# OPENMV4_BASE_ascii.net
KiCad netlist of a schematic drawn in Altium Designer
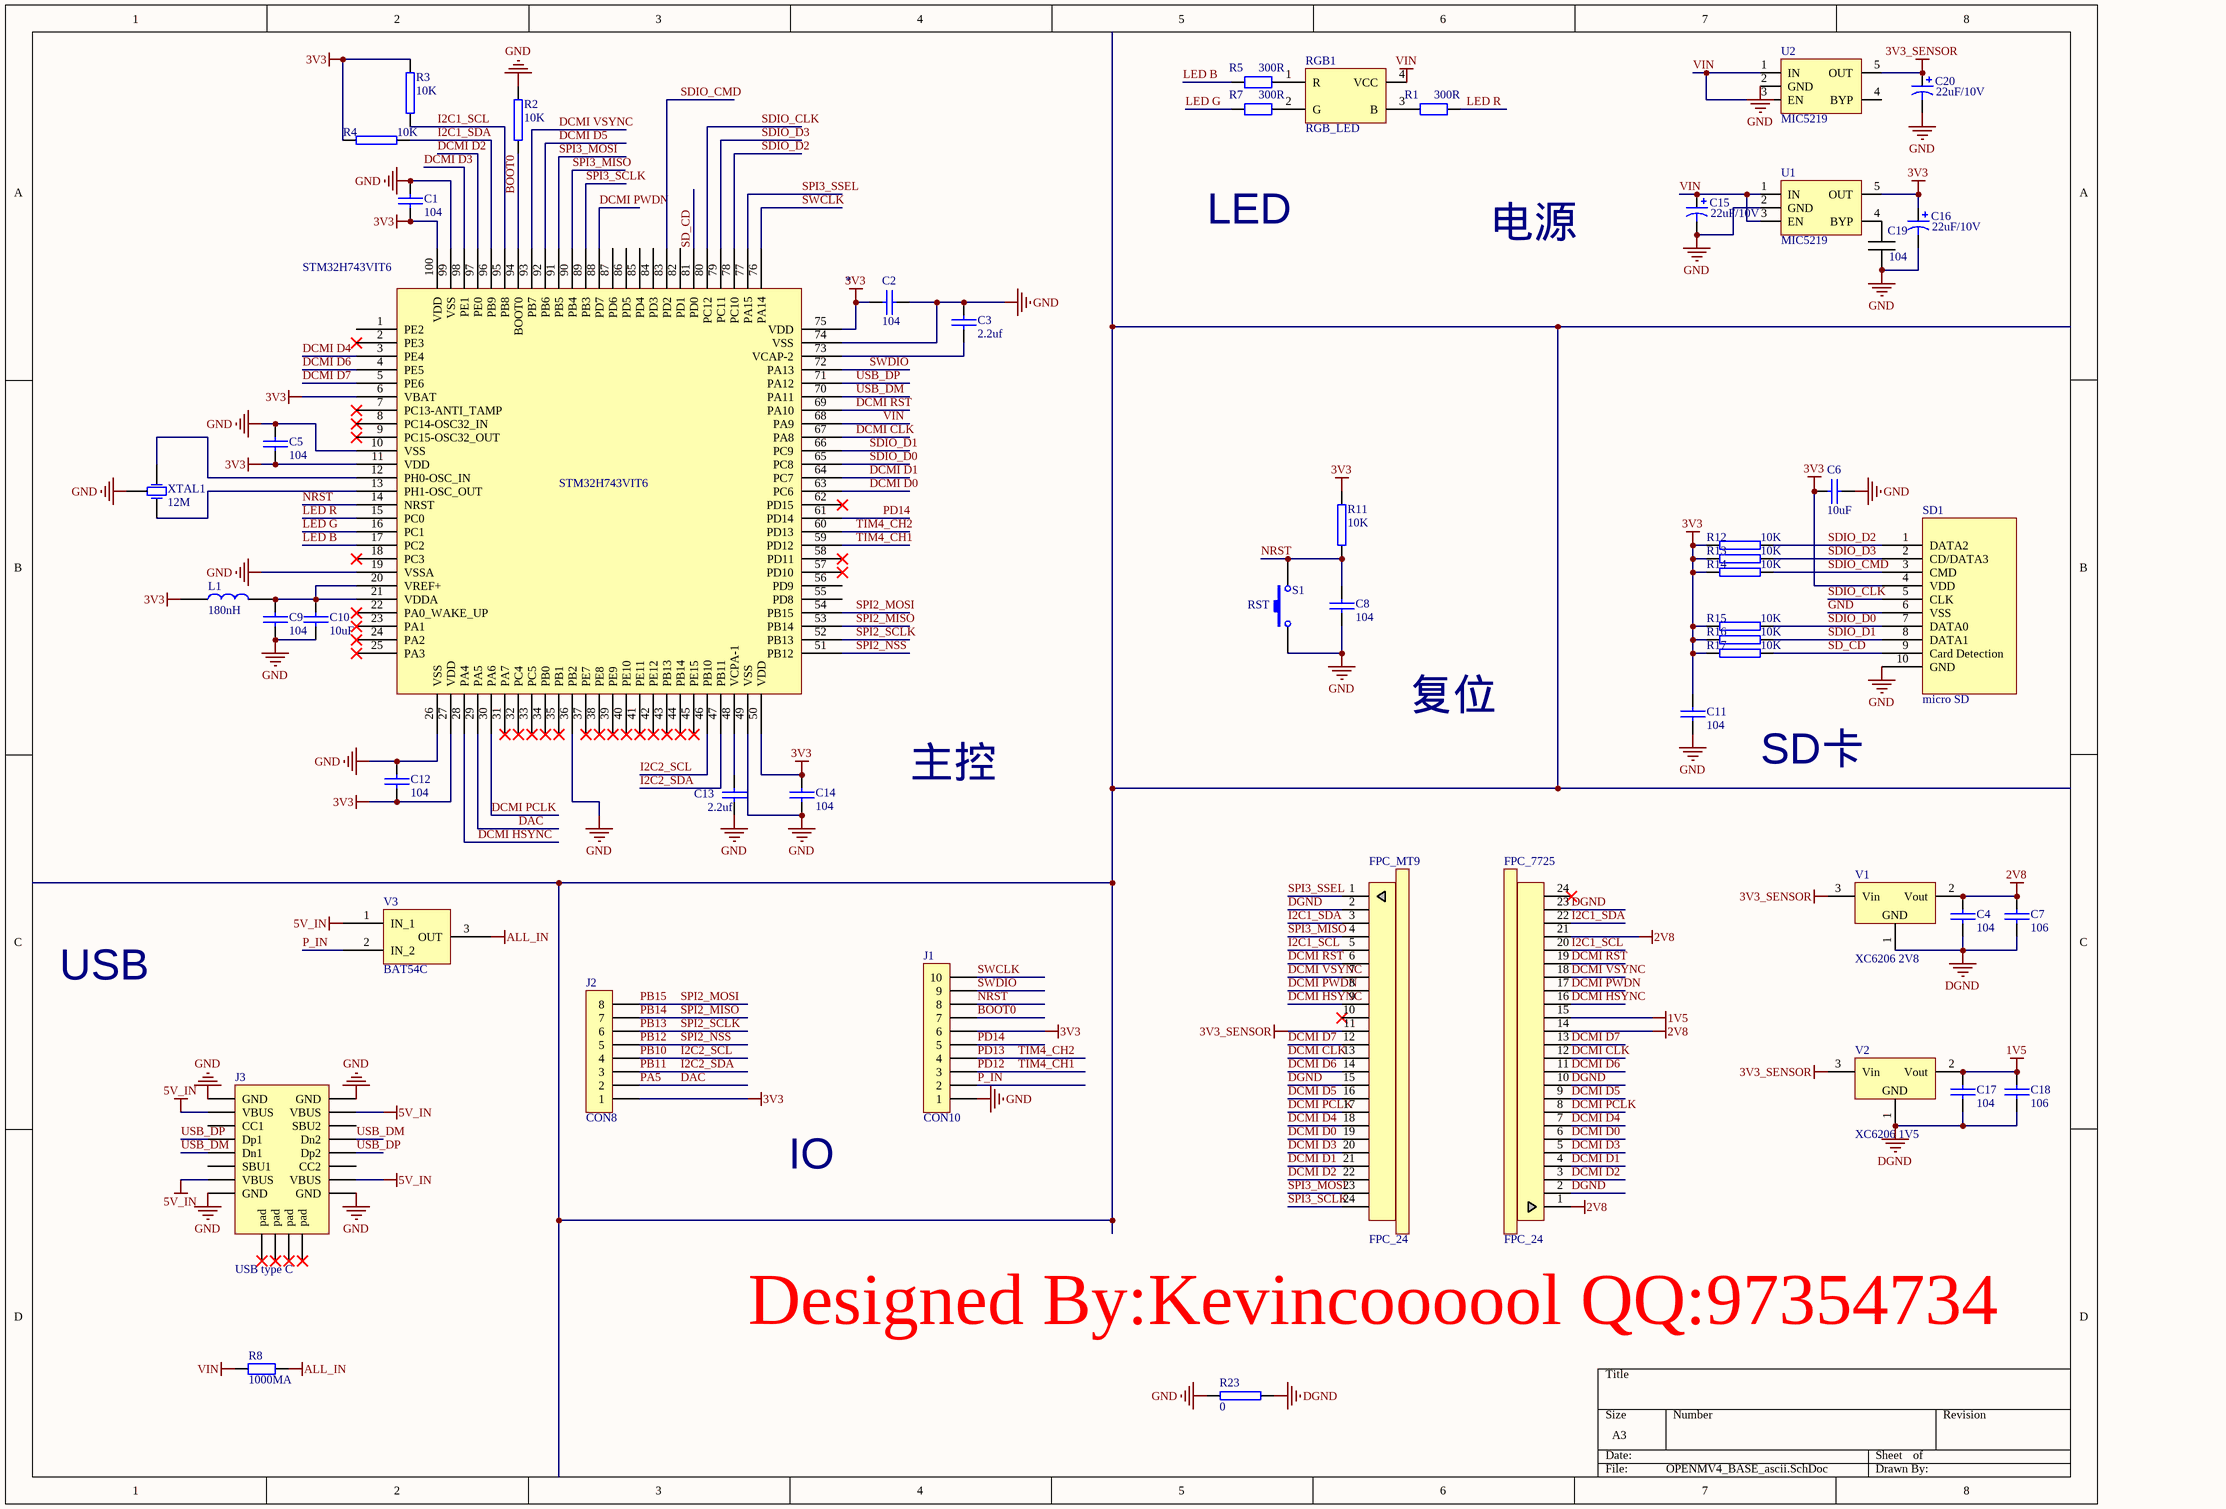
[diagram p0: OPENMV4_BASE_ascii.SchDoc]

(export (version "E")
  (design (tool "Eeschema 10.0.6"))
  (components
    (comp (ref "*")
      (value "STM32H743VIT6")
      (footprint "LQFP100 14x14_N")
      (libsource (lib "XKZ") (part "STM32H743VIT6"))
    )
    (comp (ref "C1") (value "104") (footprint "LC-0603_C") (libsource (lib "自创 (1)") (part "CAP")))
    (comp (ref "C2") (value "104") (footprint "LC-0603_C") (libsource (lib "自创 (1)") (part "CAP")))
    (comp (ref "C3") (value "2.2uf") (footprint "LC-0603_C") (libsource (lib "自创 (1)") (part "CAP")))
    (comp (ref "C4") (value "104") (footprint "0603_C") (libsource (lib "XKZ") (part "CAP")))
    (comp (ref "C5") (value "104") (footprint "LC-0603_C") (libsource (lib "自创 (1)") (part "CAP")))
    (comp (ref "C6") (value "10uF") (footprint "LC-0805_C") (libsource (lib "自创 (1)") (part "CAP")))
    (comp (ref "C7") (value "106") (footprint "0603_C") (libsource (lib "XKZ") (part "CAP")))
    (comp (ref "C8") (value "104") (footprint "LC-0603_C") (libsource (lib "自创 (1)") (part "CAP")))
    (comp (ref "C9") (value "104") (footprint "LC-0603_C") (libsource (lib "自创 (1)") (part "CAP")))
    (comp (ref "C10") (value "10uF") (footprint "LC-0603_C") (libsource (lib "自创 (1)") (part "CAP")))
    (comp (ref "C11") (value "104") (footprint "LC-0603_C") (libsource (lib "自创 (1)") (part "CAP")))
    (comp (ref "C12") (value "104") (footprint "LC-0603_C") (libsource (lib "自创 (1)") (part "CAP")))
    (comp (ref "C13") (value "2.2uf") (footprint "LC-0603_C") (libsource (lib "自创 (1)") (part "CAP")))
    (comp (ref "C14") (value "104") (footprint "LC-0603_C") (libsource (lib "自创 (1)") (part "CAP")))
    (comp (ref "C15")
      (value "22uF/10V")
      (footprint "LC-1206_C")
      (description "Polarized Capacitor (Radial)")
      (fields (field (name "Comment") "47uF") (field (name "PUBLISHER") "Altium Limited"))
      (libsource (lib "Miscellaneous Devices") (part "Cap Pol1"))
    )
    (comp (ref "C16")
      (value "22uF/10V")
      (footprint "LC-1206_C")
      (description "Polarized Capacitor (Radial)")
      (fields (field (name "Comment") "47uF") (field (name "PUBLISHER") "Altium Limited"))
      (libsource (lib "Miscellaneous Devices") (part "Cap Pol1"))
    )
    (comp (ref "C17") (value "104") (footprint "0603_C") (libsource (lib "XKZ") (part "CAP")))
    (comp (ref "C18") (value "106") (footprint "0603_C") (libsource (lib "XKZ") (part "CAP")))
    (comp (ref "C19") (value "104") (footprint "LC-0603_C") (libsource (lib "NT-SchLibrary") (part "CAP104")))
    (comp (ref "C20")
      (value "22uF/10V")
      (footprint "LC-1206_C")
      (description "Polarized Capacitor (Radial)")
      (fields (field (name "Comment") "47uF") (field (name "PUBLISHER") "Altium Limited"))
      (libsource (lib "Miscellaneous Devices") (part "Cap Pol1"))
    )
    (comp (ref "FPC_7725") (value "FPC_24") (footprint "FPC_24") (libsource (lib "XKZ") (part "FPC_24")))
    (comp (ref "FPC_MT9") (value "FPC_24") (footprint "FPC_24") (libsource (lib "") (part "FPC_24_1")))
    (comp (ref "J1") (value "CON10") (footprint "HDR1X10") (libsource (lib "自创") (part "CON10")))
    (comp (ref "J2") (value "CON8") (footprint "HDR1X8") (libsource (lib "自创") (part "CON8")))
    (comp (ref "J3")
      (value "USB type C")
      (footprint "USB Type-C-16Pin_A")
      (libsource (lib "XKZ") (part "USB_C"))
    )
    (comp (ref "L1") (value "180nH") (footprint "LC-0603_L") (libsource (lib "自创 (1)") (part "Inductor")))
    (comp (ref "R1")
      (value "300R")
      (footprint "0603_R")
      (description "Resistor")
      (fields (field (name "Comment") "1K") (field (name "PUBLISHER") "Altium Limited"))
      (libsource (lib "Miscellaneous Devices") (part "Res2"))
    )
    (comp (ref "R2") (value "10K") (footprint "LC-0603_R") (libsource (lib "自创 (1)") (part "RES")))
    (comp (ref "R3") (value "10K") (footprint "LC-0603_R") (libsource (lib "自创 (1)") (part "RES")))
    (comp (ref "R4") (value "10K") (footprint "LC-0603_R") (libsource (lib "自创 (1)") (part "RES")))
    (comp (ref "R5")
      (value "300R")
      (footprint "0603_R")
      (description "Resistor")
      (fields (field (name "Comment") "1K") (field (name "PUBLISHER") "Altium Limited"))
      (libsource (lib "Miscellaneous Devices") (part "Res2"))
    )
    (comp (ref "R7")
      (value "300R")
      (footprint "0603_R")
      (description "Resistor")
      (fields (field (name "Comment") "1K") (field (name "PUBLISHER") "Altium Limited"))
      (libsource (lib "Miscellaneous Devices") (part "Res2"))
    )
    (comp (ref "R8")
      (value "1000MA")
      (footprint "LC-0805_L")
      (description "Resistor")
      (fields (field (name "Comment") "1A保险丝") (field (name "PUBLISHER") "Altium Limited"))
      (libsource (lib "XKZ") (part "Res2"))
    )
    (comp (ref "R11") (value "10K") (footprint "LC-0603_R") (libsource (lib "自创 (1)") (part "RES")))
    (comp (ref "R12") (value "10K") (footprint "LC-0603_R") (libsource (lib "自创 (1)") (part "RES")))
    (comp (ref "R13") (value "10K") (footprint "LC-0603_R") (libsource (lib "自创 (1)") (part "RES")))
    (comp (ref "R14") (value "10K") (footprint "LC-0603_R") (libsource (lib "自创 (1)") (part "RES")))
    (comp (ref "R15") (value "10K") (footprint "LC-0603_R") (libsource (lib "自创 (1)") (part "RES")))
    (comp (ref "R16") (value "10K") (footprint "LC-0603_R") (libsource (lib "自创 (1)") (part "RES")))
    (comp (ref "R17") (value "10K") (footprint "LC-0603_R") (libsource (lib "自创 (1)") (part "RES")))
    (comp (ref "R23") (value "0") (footprint "LC-0603_R") (libsource (lib "自创 (1)") (part "RES")))
    (comp (ref "RGB1")
      (value "RGB_LED")
      (footprint "LED_3528_RGB")
      (description "三色高亮LED")
      (libsource (lib "NT-SchLibrary") (part "RGB_LED"))
    )
    (comp (ref "S1")
      (value "RST")
      (footprint "KEY_1")
      (description "Switch")
      (fields (field (name "PUBLISHER") "Altium Limited"))
      (libsource (lib "自创 (1)") (part "SW-PB"))
    )
    (comp (ref "SD1") (value "micro SD") (footprint "TF卡座") (libsource (lib "XKZ") (part "micro SD")))
    (comp (ref "U1")
      (value "MIC5219")
      (footprint "SOT23-5N")
      (description "3.3V 降压芯片")
      (libsource (lib "NT-SchLibrary") (part "MIC5219"))
    )
    (comp (ref "U2")
      (value "MIC5219")
      (footprint "SOT23-5N")
      (description "3.3V 降压芯片")
      (libsource (lib "NT-SchLibrary") (part "MIC5219"))
    )
    (comp (ref "V1")
      (value "XC6206 2V8")
      (footprint "SOT23-3N")
      (description "低压差线性稳压芯片")
      (fields (field (name "版权归属") "源创客"))
      (libsource (lib "XKZ") (part "XC6206P332MR"))
    )
    (comp (ref "V2")
      (value "XC6206 1V5")
      (footprint "SOT23-3N")
      (description "低压差线性稳压芯片")
      (fields (field (name "版权归属") "源创客"))
      (libsource (lib "XKZ") (part "XC6206P332MR"))
    )
    (comp (ref "V3") (value "BAT54C") (footprint "SOT23-3N") (libsource (lib "XKZ") (part "BAT54C")))
    (comp (ref "XTAL1") (value "12M") (footprint "XTAL-3215-3P") (libsource (lib "XKZ") (part "XTAL_3P")))
  )
  (nets
    (net (code "1") (name "/BOOT0") (class "Default")
      (node (ref "*") (pin "94") (pinfunction "BOOT0_94") (pintype "passive"))
      (node (ref "J1") (pin "7") (pinfunction "7_7") (pintype "passive"))
      (node (ref "R2") (pin "1") (pinfunction "1_1") (pintype "passive"))
    )
    (net (code "2") (name "/DAC") (class "Default")
      (node (ref "*") (pin "29") (pinfunction "PA5_29") (pintype "passive"))
      (node (ref "J2") (pin "2") (pinfunction "2_2") (pintype "passive"))
    )
    (net (code "3") (name "/DCMI CLK") (class "Default")
      (node (ref "*") (pin "67") (pinfunction "PA8_67") (pintype "passive"))
      (node (ref "FPC_7725") (pin "12") (pinfunction "12_12") (pintype "passive"))
      (node (ref "FPC_MT9") (pin "13") (pinfunction "13_13") (pintype "passive"))
    )
    (net (code "4") (name "/DCMI D0") (class "Default")
      (node (ref "*") (pin "63") (pinfunction "PC6_63") (pintype "passive"))
      (node (ref "FPC_7725") (pin "6") (pinfunction "6_6") (pintype "passive"))
      (node (ref "FPC_MT9") (pin "19") (pinfunction "19_19") (pintype "passive"))
    )
    (net (code "5") (name "/DCMI D1") (class "Default")
      (node (ref "*") (pin "64") (pinfunction "PC7_64") (pintype "passive"))
      (node (ref "FPC_7725") (pin "4") (pinfunction "4_4") (pintype "passive"))
      (node (ref "FPC_MT9") (pin "21") (pinfunction "21_21") (pintype "passive"))
    )
    (net (code "6") (name "/DCMI D2") (class "Default")
      (node (ref "*") (pin "97") (pinfunction "PE0_97") (pintype "passive"))
      (node (ref "FPC_7725") (pin "3") (pinfunction "3_3") (pintype "passive"))
      (node (ref "FPC_MT9") (pin "22") (pinfunction "22_22") (pintype "passive"))
    )
    (net (code "7") (name "/DCMI D3") (class "Default")
      (node (ref "*") (pin "98") (pinfunction "PE1_98") (pintype "passive"))
      (node (ref "FPC_7725") (pin "5") (pinfunction "5_5") (pintype "passive"))
      (node (ref "FPC_MT9") (pin "20") (pinfunction "20_20") (pintype "passive"))
    )
    (net (code "8") (name "/DCMI D4") (class "Default")
      (node (ref "*") (pin "3") (pinfunction "PE4_3") (pintype "passive"))
      (node (ref "FPC_7725") (pin "7") (pinfunction "7_7") (pintype "passive"))
      (node (ref "FPC_MT9") (pin "18") (pinfunction "18_18") (pintype "passive"))
    )
    (net (code "9") (name "/DCMI D5") (class "Default")
      (node (ref "*") (pin "92") (pinfunction "PB6_92") (pintype "passive"))
      (node (ref "FPC_7725") (pin "9") (pinfunction "9_9") (pintype "passive"))
      (node (ref "FPC_MT9") (pin "16") (pinfunction "16_16") (pintype "passive"))
    )
    (net (code "10") (name "/DCMI D6") (class "Default")
      (node (ref "*") (pin "4") (pinfunction "PE5_4") (pintype "passive"))
      (node (ref "FPC_7725") (pin "11") (pinfunction "11_11") (pintype "passive"))
      (node (ref "FPC_MT9") (pin "14") (pinfunction "14_14") (pintype "passive"))
    )
    (net (code "11") (name "/DCMI D7") (class "Default")
      (node (ref "*") (pin "5") (pinfunction "PE6_5") (pintype "passive"))
      (node (ref "FPC_7725") (pin "13") (pinfunction "13_13") (pintype "passive"))
      (node (ref "FPC_MT9") (pin "12") (pinfunction "12_12") (pintype "passive"))
    )
    (net (code "12") (name "/DCMI HSYNC") (class "Default")
      (node (ref "*") (pin "28") (pinfunction "PA4_28") (pintype "passive"))
      (node (ref "FPC_7725") (pin "16") (pinfunction "16_16") (pintype "passive"))
      (node (ref "FPC_MT9") (pin "9") (pinfunction "9_9") (pintype "passive"))
    )
    (net (code "13") (name "/DCMI PCLK") (class "Default")
      (node (ref "*") (pin "30") (pinfunction "PA6_30") (pintype "passive"))
      (node (ref "FPC_7725") (pin "8") (pinfunction "8_8") (pintype "passive"))
      (node (ref "FPC_MT9") (pin "17") (pinfunction "17_17") (pintype "passive"))
    )
    (net (code "14") (name "/DCMI PWDN") (class "Default")
      (node (ref "*") (pin "88") (pinfunction "PD7_88") (pintype "passive"))
      (node (ref "FPC_7725") (pin "17") (pinfunction "17_17") (pintype "passive"))
      (node (ref "FPC_MT9") (pin "8") (pinfunction "8_8") (pintype "passive"))
    )
    (net (code "15") (name "/DCMI RST") (class "Default")
      (node (ref "*") (pin "69") (pinfunction "PA10_69") (pintype "passive"))
      (node (ref "FPC_7725") (pin "19") (pinfunction "19_19") (pintype "passive"))
      (node (ref "FPC_MT9") (pin "6") (pinfunction "6_6") (pintype "passive"))
    )
    (net (code "16") (name "/DCMI VSYNC") (class "Default")
      (node (ref "*") (pin "93") (pinfunction "PB7_93") (pintype "passive"))
      (node (ref "FPC_7725") (pin "18") (pinfunction "18_18") (pintype "passive"))
      (node (ref "FPC_MT9") (pin "7") (pinfunction "7_7") (pintype "passive"))
    )
    (net (code "17") (name "/I2C1_SCL") (class "Default")
      (node (ref "*") (pin "95") (pinfunction "PB8_95") (pintype "passive"))
      (node (ref "FPC_7725") (pin "20") (pinfunction "20_20") (pintype "passive"))
      (node (ref "FPC_MT9") (pin "5") (pinfunction "5_5") (pintype "passive"))
      (node (ref "R3") (pin "1") (pinfunction "1_1") (pintype "passive"))
    )
    (net (code "18") (name "/I2C1_SDA") (class "Default")
      (node (ref "*") (pin "96") (pinfunction "PB9_96") (pintype "passive"))
      (node (ref "FPC_7725") (pin "22") (pinfunction "22_22") (pintype "passive"))
      (node (ref "FPC_MT9") (pin "3") (pinfunction "3_3") (pintype "passive"))
      (node (ref "R4") (pin "2") (pinfunction "2_2") (pintype "passive"))
    )
    (net (code "19") (name "/I2C2_SCL") (class "Default")
      (node (ref "*") (pin "46") (pinfunction "PB10_46") (pintype "passive"))
      (node (ref "J2") (pin "4") (pinfunction "4_4") (pintype "passive"))
    )
    (net (code "20") (name "/I2C2_SDA") (class "Default")
      (node (ref "*") (pin "47") (pinfunction "PB11_47") (pintype "passive"))
      (node (ref "J2") (pin "3") (pinfunction "3_3") (pintype "passive"))
    )
    (net (code "21") (name "/LED B") (class "Default")
      (node (ref "*") (pin "17") (pinfunction "PC2_17") (pintype "passive"))
      (node (ref "R5") (pin "1") (pinfunction "1_1") (pintype "passive"))
    )
    (net (code "22") (name "/LED G") (class "Default")
      (node (ref "*") (pin "16") (pinfunction "PC1_16") (pintype "passive"))
      (node (ref "R7") (pin "1") (pinfunction "1_1") (pintype "passive"))
    )
    (net (code "23") (name "/LED R") (class "Default")
      (node (ref "*") (pin "15") (pinfunction "PC0_15") (pintype "passive"))
      (node (ref "R1") (pin "2") (pinfunction "2_2") (pintype "passive"))
    )
    (net (code "24") (name "/NRST") (class "Default")
      (node (ref "*") (pin "14") (pinfunction "NRST_14") (pintype "passive"))
      (node (ref "C8") (pin "2") (pinfunction "2_2") (pintype "passive"))
      (node (ref "J1") (pin "8") (pinfunction "8_8") (pintype "passive"))
      (node (ref "R11") (pin "2") (pinfunction "2_2") (pintype "passive"))
      (node (ref "S1") (pin "2") (pinfunction "2_2") (pintype "passive"))
    )
    (net (code "25") (name "/PB12") (class "Default")
      (node (ref "*") (pin "51") (pinfunction "PB12_51") (pintype "passive"))
      (node (ref "J2") (pin "5") (pinfunction "5_5") (pintype "passive"))
    )
    (net (code "26") (name "/PB13") (class "Default")
      (node (ref "*") (pin "52") (pinfunction "PB13_52") (pintype "passive"))
      (node (ref "J2") (pin "6") (pinfunction "6_6") (pintype "passive"))
    )
    (net (code "27") (name "/PB14") (class "Default")
      (node (ref "*") (pin "53") (pinfunction "PB14_53") (pintype "passive"))
      (node (ref "J2") (pin "7") (pinfunction "7_7") (pintype "passive"))
    )
    (net (code "28") (name "/PB15") (class "Default")
      (node (ref "*") (pin "54") (pinfunction "PB15_54") (pintype "passive"))
      (node (ref "J2") (pin "8") (pinfunction "8_8") (pintype "passive"))
    )
    (net (code "29") (name "/PD12") (class "Default")
      (node (ref "*") (pin "59") (pinfunction "PD12_59") (pintype "passive"))
      (node (ref "J1") (pin "3") (pinfunction "3_3") (pintype "passive"))
    )
    (net (code "30") (name "/PD13") (class "Default")
      (node (ref "*") (pin "60") (pinfunction "PD13_60") (pintype "passive"))
      (node (ref "J1") (pin "4") (pinfunction "4_4") (pintype "passive"))
    )
    (net (code "31") (name "/PD14") (class "Default")
      (node (ref "*") (pin "61") (pinfunction "PD14_61") (pintype "passive"))
      (node (ref "J1") (pin "5") (pinfunction "5_5") (pintype "passive"))
    )
    (net (code "32") (name "/P_IN") (class "Default")
      (node (ref "J1") (pin "2") (pinfunction "2_2") (pintype "passive"))
      (node (ref "V3") (pin "2") (pinfunction "IN_2_2") (pintype "passive"))
    )
    (net (code "33") (name "/SDIO_CLK") (class "Default")
      (node (ref "*") (pin "80") (pinfunction "PC12_80") (pintype "passive"))
      (node (ref "SD1") (pin "5") (pinfunction "CLK_5") (pintype "passive"))
    )
    (net (code "34") (name "/SDIO_CMD") (class "Default")
      (node (ref "*") (pin "83") (pinfunction "PD2_83") (pintype "passive"))
      (node (ref "R14") (pin "2") (pinfunction "2_2") (pintype "passive"))
      (node (ref "SD1") (pin "3") (pinfunction "CMD_3") (pintype "passive"))
    )
    (net (code "35") (name "/SDIO_D0") (class "Default")
      (node (ref "*") (pin "65") (pinfunction "PC8_65") (pintype "passive"))
      (node (ref "R15") (pin "2") (pinfunction "2_2") (pintype "passive"))
      (node (ref "SD1") (pin "7") (pinfunction "DATA0_7") (pintype "passive"))
    )
    (net (code "36") (name "/SDIO_D1") (class "Default")
      (node (ref "*") (pin "66") (pinfunction "PC9_66") (pintype "passive"))
      (node (ref "R16") (pin "2") (pinfunction "2_2") (pintype "passive"))
      (node (ref "SD1") (pin "8") (pinfunction "DATA1_8") (pintype "passive"))
    )
    (net (code "37") (name "/SDIO_D2") (class "Default")
      (node (ref "*") (pin "78") (pinfunction "PC10_78") (pintype "passive"))
      (node (ref "R12") (pin "2") (pinfunction "2_2") (pintype "passive"))
      (node (ref "SD1") (pin "1") (pinfunction "DATA2_1") (pintype "passive"))
    )
    (net (code "38") (name "/SDIO_D3") (class "Default")
      (node (ref "*") (pin "79") (pinfunction "PC11_79") (pintype "passive"))
      (node (ref "R13") (pin "2") (pinfunction "2_2") (pintype "passive"))
      (node (ref "SD1") (pin "2") (pinfunction "CD/DATA3_2") (pintype "passive"))
    )
    (net (code "39") (name "/SD_CD") (class "Default")
      (node (ref "*") (pin "81") (pinfunction "PD0_81") (pintype "passive"))
      (node (ref "R17") (pin "2") (pinfunction "2_2") (pintype "passive"))
      (node (ref "SD1") (pin "9") (pinfunction "Card_Detection_9") (pintype "passive"))
    )
    (net (code "40") (name "/SPI3_MISO") (class "Default")
      (node (ref "*") (pin "90") (pinfunction "PB4_90") (pintype "passive"))
      (node (ref "FPC_MT9") (pin "4") (pinfunction "4_4") (pintype "passive"))
    )
    (net (code "41") (name "/SPI3_MOSI") (class "Default")
      (node (ref "*") (pin "91") (pinfunction "PB5_91") (pintype "passive"))
      (node (ref "FPC_MT9") (pin "23") (pinfunction "23_23") (pintype "passive"))
    )
    (net (code "42") (name "/SPI3_SCLK") (class "Default")
      (node (ref "*") (pin "89") (pinfunction "PB3_89") (pintype "passive"))
      (node (ref "FPC_MT9") (pin "24") (pinfunction "24_24") (pintype "passive"))
    )
    (net (code "43") (name "/SPI3_SSEL") (class "Default")
      (node (ref "*") (pin "77") (pinfunction "PA15_77") (pintype "passive"))
      (node (ref "FPC_MT9") (pin "1") (pinfunction "1_1") (pintype "passive"))
    )
    (net (code "44") (name "/SWCLK") (class "Default")
      (node (ref "*") (pin "76") (pinfunction "PA14_76") (pintype "passive"))
      (node (ref "J1") (pin "10") (pinfunction "10_10") (pintype "passive"))
    )
    (net (code "45") (name "/SWDIO") (class "Default")
      (node (ref "*") (pin "72") (pinfunction "PA13_72") (pintype "passive"))
      (node (ref "J1") (pin "9") (pinfunction "9_9") (pintype "passive"))
    )
    (net (code "46") (name "/USB_DM") (class "Default")
      (node (ref "*") (pin "70") (pinfunction "PA11_70") (pintype "passive"))
      (node (ref "J3") (pin "A7") (pinfunction "Dn1_A7") (pintype "passive"))
      (node (ref "J3") (pin "B7") (pinfunction "Dn2_B7") (pintype "passive"))
    )
    (net (code "47") (name "/USB_DP") (class "Default")
      (node (ref "*") (pin "71") (pinfunction "PA12_71") (pintype "passive"))
      (node (ref "J3") (pin "A6") (pinfunction "Dp1_A6") (pintype "passive"))
      (node (ref "J3") (pin "B6") (pinfunction "Dp2_B6") (pintype "passive"))
    )
    (net (code "48") (name "1V5") (class "Default")
      (node (ref "C17") (pin "1") (pinfunction "1_1") (pintype "passive"))
      (node (ref "C18") (pin "1") (pinfunction "1_1") (pintype "passive"))
      (node (ref "FPC_7725") (pin "15") (pinfunction "15_15") (pintype "passive"))
      (node (ref "V2") (pin "2") (pinfunction "Vout_2") (pintype "passive"))
    )
    (net (code "49") (name "2V8") (class "Default")
      (node (ref "C4") (pin "1") (pinfunction "1_1") (pintype "passive"))
      (node (ref "C7") (pin "1") (pinfunction "1_1") (pintype "passive"))
      (node (ref "FPC_7725") (pin "1") (pinfunction "1_1") (pintype "passive"))
      (node (ref "FPC_7725") (pin "14") (pinfunction "14_14") (pintype "passive"))
      (node (ref "FPC_7725") (pin "21") (pinfunction "21_21") (pintype "passive"))
      (node (ref "V1") (pin "2") (pinfunction "Vout_2") (pintype "passive"))
    )
    (net (code "50") (name "3V3") (class "Default")
      (node (ref "*") (pin "100") (pinfunction "VDD_100") (pintype "passive"))
      (node (ref "*") (pin "11") (pinfunction "VDD_11") (pintype "passive"))
      (node (ref "*") (pin "27") (pinfunction "VDD_27") (pintype "passive"))
      (node (ref "*") (pin "50") (pinfunction "VDD_50") (pintype "passive"))
      (node (ref "*") (pin "6") (pinfunction "VBAT_6") (pintype "passive"))
      (node (ref "*") (pin "75") (pinfunction "VDD_75") (pintype "passive"))
      (node (ref "C1") (pin "2") (pinfunction "2_2") (pintype "passive"))
      (node (ref "C11") (pin "2") (pinfunction "2_2") (pintype "passive"))
      (node (ref "C12") (pin "2") (pinfunction "2_2") (pintype "passive"))
      (node (ref "C14") (pin "2") (pinfunction "2_2") (pintype "passive"))
      (node (ref "C16") (pin "1") (pinfunction "1_1") (pintype "passive"))
      (node (ref "C2") (pin "2") (pinfunction "2_2") (pintype "passive"))
      (node (ref "C5") (pin "2") (pinfunction "2_2") (pintype "passive"))
      (node (ref "C6") (pin "2") (pinfunction "2_2") (pintype "passive"))
      (node (ref "J1") (pin "6") (pinfunction "6_6") (pintype "passive"))
      (node (ref "J2") (pin "1") (pinfunction "1_1") (pintype "passive"))
      (node (ref "L1") (pin "1") (pinfunction "1_1") (pintype "passive"))
      (node (ref "R11") (pin "1") (pinfunction "1_1") (pintype "passive"))
      (node (ref "R12") (pin "1") (pinfunction "1_1") (pintype "passive"))
      (node (ref "R13") (pin "1") (pinfunction "1_1") (pintype "passive"))
      (node (ref "R14") (pin "1") (pinfunction "1_1") (pintype "passive"))
      (node (ref "R15") (pin "1") (pinfunction "1_1") (pintype "passive"))
      (node (ref "R16") (pin "1") (pinfunction "1_1") (pintype "passive"))
      (node (ref "R17") (pin "1") (pinfunction "1_1") (pintype "passive"))
      (node (ref "R3") (pin "2") (pinfunction "2_2") (pintype "passive"))
      (node (ref "R4") (pin "1") (pinfunction "1_1") (pintype "passive"))
      (node (ref "SD1") (pin "4") (pinfunction "VDD_4") (pintype "passive"))
      (node (ref "U1") (pin "5") (pinfunction "OUT_5") (pintype "passive"))
    )
    (net (code "51") (name "3V3_SENSOR") (class "Default")
      (node (ref "C20") (pin "1") (pinfunction "1_1") (pintype "passive"))
      (node (ref "FPC_MT9") (pin "11") (pinfunction "11_11") (pintype "passive"))
      (node (ref "U2") (pin "5") (pinfunction "OUT_5") (pintype "passive"))
      (node (ref "V1") (pin "3") (pinfunction "Vin_3") (pintype "passive"))
      (node (ref "V2") (pin "3") (pinfunction "Vin_3") (pintype "passive"))
    )
    (net (code "52") (name "5V_IN") (class "Default")
      (node (ref "J3") (pin "A4") (pinfunction "VBUS_A4") (pintype "passive"))
      (node (ref "J3") (pin "A9") (pinfunction "VBUS_A9") (pintype "passive"))
      (node (ref "J3") (pin "B4") (pinfunction "VBUS_B4") (pintype "passive"))
      (node (ref "J3") (pin "B9") (pinfunction "VBUS_B9") (pintype "passive"))
      (node (ref "V3") (pin "1") (pinfunction "IN_1_1") (pintype "passive"))
    )
    (net (code "53") (name "ALL_IN") (class "Default")
      (node (ref "R8") (pin "2") (pinfunction "2_2") (pintype "passive"))
      (node (ref "V3") (pin "3") (pinfunction "OUT_3") (pintype "passive"))
    )
    (net (code "54") (name "DGND") (class "Default")
      (node (ref "C17") (pin "2") (pinfunction "2_2") (pintype "passive"))
      (node (ref "C18") (pin "2") (pinfunction "2_2") (pintype "passive"))
      (node (ref "C4") (pin "2") (pinfunction "2_2") (pintype "passive"))
      (node (ref "C7") (pin "2") (pinfunction "2_2") (pintype "passive"))
      (node (ref "FPC_7725") (pin "10") (pinfunction "10_10") (pintype "passive"))
      (node (ref "FPC_7725") (pin "2") (pinfunction "2_2") (pintype "passive"))
      (node (ref "FPC_7725") (pin "23") (pinfunction "23_23") (pintype "passive"))
      (node (ref "FPC_MT9") (pin "15") (pinfunction "15_15") (pintype "passive"))
      (node (ref "FPC_MT9") (pin "2") (pinfunction "2_2") (pintype "passive"))
      (node (ref "R23") (pin "2") (pinfunction "2_2") (pintype "passive"))
      (node (ref "V1") (pin "1") (pinfunction "GND_1") (pintype "passive"))
      (node (ref "V2") (pin "1") (pinfunction "GND_1") (pintype "passive"))
    )
    (net (code "55") (name "GND") (class "Default")
      (node (ref "*") (pin "10") (pinfunction "VSS_10") (pintype "passive"))
      (node (ref "*") (pin "19") (pinfunction "VSSA_19") (pintype "passive"))
      (node (ref "*") (pin "26") (pinfunction "VSS_26") (pintype "passive"))
      (node (ref "*") (pin "36") (pinfunction "PB2_36") (pintype "passive"))
      (node (ref "*") (pin "49") (pinfunction "VSS_49") (pintype "passive"))
      (node (ref "*") (pin "74") (pinfunction "VSS_74") (pintype "passive"))
      (node (ref "*") (pin "99") (pinfunction "VSS_99") (pintype "passive"))
      (node (ref "C1") (pin "1") (pinfunction "1_1") (pintype "passive"))
      (node (ref "C10") (pin "2") (pinfunction "2_2") (pintype "passive"))
      (node (ref "C11") (pin "1") (pinfunction "1_1") (pintype "passive"))
      (node (ref "C12") (pin "1") (pinfunction "1_1") (pintype "passive"))
      (node (ref "C13") (pin "2") (pinfunction "2_2") (pintype "passive"))
      (node (ref "C14") (pin "1") (pinfunction "1_1") (pintype "passive"))
      (node (ref "C15") (pin "2") (pinfunction "2_2") (pintype "passive"))
      (node (ref "C16") (pin "2") (pinfunction "2_2") (pintype "passive"))
      (node (ref "C19") (pin "1") (pinfunction "1_1") (pintype "passive"))
      (node (ref "C2") (pin "1") (pinfunction "1_1") (pintype "passive"))
      (node (ref "C20") (pin "2") (pinfunction "2_2") (pintype "passive"))
      (node (ref "C3") (pin "2") (pinfunction "2_2") (pintype "passive"))
      (node (ref "C5") (pin "1") (pinfunction "1_1") (pintype "passive"))
      (node (ref "C6") (pin "1") (pinfunction "1_1") (pintype "passive"))
      (node (ref "C8") (pin "1") (pinfunction "1_1") (pintype "passive"))
      (node (ref "C9") (pin "2") (pinfunction "2_2") (pintype "passive"))
      (node (ref "J1") (pin "1") (pinfunction "1_1") (pintype "passive"))
      (node (ref "J3") (pin "A1") (pinfunction "GND_A1") (pintype "passive"))
      (node (ref "J3") (pin "A12") (pinfunction "GND_A12") (pintype "passive"))
      (node (ref "J3") (pin "B1") (pinfunction "GND_B1") (pintype "passive"))
      (node (ref "J3") (pin "B12") (pinfunction "GND_B12") (pintype "passive"))
      (node (ref "R2") (pin "2") (pinfunction "2_2") (pintype "passive"))
      (node (ref "R23") (pin "1") (pinfunction "1_1") (pintype "passive"))
      (node (ref "S1") (pin "1") (pinfunction "1_1") (pintype "passive"))
      (node (ref "SD1") (pin "10") (pinfunction "GND_10") (pintype "passive"))
      (node (ref "SD1") (pin "6") (pinfunction "VSS_6") (pintype "passive"))
      (node (ref "U1") (pin "2") (pinfunction "GND_2") (pintype "passive"))
      (node (ref "U2") (pin "2") (pinfunction "GND_2") (pintype "passive"))
      (node (ref "XTAL1") (pin "2") (pinfunction "2_2") (pintype "passive"))
    )
    (net (code "56") (name "Net-(*-PH0-OSC_IN)") (class "Default")
      (node (ref "*") (pin "12") (pinfunction "PH0-OSC_IN_12") (pintype "passive"))
      (node (ref "XTAL1") (pin "1") (pinfunction "1_1") (pintype "passive"))
    )
    (net (code "57") (name "Net-(*-PH1-OSC_OUT)") (class "Default")
      (node (ref "*") (pin "13") (pinfunction "PH1-OSC_OUT_13") (pintype "passive"))
      (node (ref "XTAL1") (pin "3") (pinfunction "3_3") (pintype "passive"))
    )
    (net (code "58") (name "Net-(*-VCAP-2)") (class "Default")
      (node (ref "*") (pin "73") (pinfunction "VCAP-2_73") (pintype "passive"))
      (node (ref "C3") (pin "1") (pinfunction "1_1") (pintype "passive"))
    )
    (net (code "59") (name "Net-(*-VCPA-1)") (class "Default")
      (node (ref "*") (pin "48") (pinfunction "VCPA-1_48") (pintype "passive"))
      (node (ref "C13") (pin "1") (pinfunction "1_1") (pintype "passive"))
    )
    (net (code "60") (name "Net-(*-VDDA)") (class "Default")
      (node (ref "*") (pin "20") (pinfunction "VREF+_20") (pintype "passive"))
      (node (ref "*") (pin "21") (pinfunction "VDDA_21") (pintype "passive"))
      (node (ref "C10") (pin "1") (pinfunction "1_1") (pintype "passive"))
      (node (ref "C9") (pin "1") (pinfunction "1_1") (pintype "passive"))
      (node (ref "L1") (pin "2") (pinfunction "2_2") (pintype "passive"))
    )
    (net (code "61") (name "Net-(RGB1-B)") (class "Default")
      (node (ref "R1") (pin "1") (pinfunction "1_1") (pintype "passive"))
      (node (ref "RGB1") (pin "3") (pinfunction "B_3") (pintype "passive"))
    )
    (net (code "62") (name "Net-(RGB1-G)") (class "Default")
      (node (ref "R7") (pin "2") (pinfunction "2_2") (pintype "passive"))
      (node (ref "RGB1") (pin "2") (pinfunction "G_2") (pintype "passive"))
    )
    (net (code "63") (name "Net-(RGB1-R)") (class "Default")
      (node (ref "R5") (pin "2") (pinfunction "2_2") (pintype "passive"))
      (node (ref "RGB1") (pin "1") (pinfunction "R_1") (pintype "passive"))
    )
    (net (code "64") (name "Net-(U1-BYP)") (class "Default")
      (node (ref "C19") (pin "2") (pinfunction "2_2") (pintype "passive"))
      (node (ref "U1") (pin "4") (pinfunction "BYP_4") (pintype "passive"))
    )
    (net (code "65") (name "VIN") (class "Default")
      (node (ref "*") (pin "68") (pinfunction "PA9_68") (pintype "passive"))
      (node (ref "C15") (pin "1") (pinfunction "1_1") (pintype "passive"))
      (node (ref "R8") (pin "1") (pinfunction "1_1") (pintype "passive"))
      (node (ref "RGB1") (pin "4") (pinfunction "VCC_4") (pintype "passive"))
      (node (ref "U1") (pin "1") (pinfunction "IN_1") (pintype "passive"))
      (node (ref "U1") (pin "3") (pinfunction "EN_3") (pintype "passive"))
      (node (ref "U2") (pin "1") (pinfunction "IN_1") (pintype "passive"))
      (node (ref "U2") (pin "3") (pinfunction "EN_3") (pintype "passive"))
    )
    (net (code "66") (name "unconnected-(*-PA0_WAKE_UP-Pad22)") (class "Default")
      (node (ref "*") (pin "22") (pinfunction "PA0_WAKE_UP_22") (pintype "passive+no_connect"))
    )
    (net (code "67") (name "unconnected-(*-PA1-Pad23)") (class "Default")
      (node (ref "*") (pin "23") (pinfunction "PA1_23") (pintype "passive+no_connect"))
    )
    (net (code "68") (name "unconnected-(*-PA2-Pad24)") (class "Default")
      (node (ref "*") (pin "24") (pinfunction "PA2_24") (pintype "passive+no_connect"))
    )
    (net (code "69") (name "unconnected-(*-PA3-Pad25)") (class "Default")
      (node (ref "*") (pin "25") (pinfunction "PA3_25") (pintype "passive+no_connect"))
    )
    (net (code "70") (name "unconnected-(*-PA7-Pad31)") (class "Default")
      (node (ref "*") (pin "31") (pinfunction "PA7_31") (pintype "passive+no_connect"))
    )
    (net (code "71") (name "unconnected-(*-PB0-Pad34)") (class "Default")
      (node (ref "*") (pin "34") (pinfunction "PB0_34") (pintype "passive+no_connect"))
    )
    (net (code "72") (name "unconnected-(*-PB1-Pad35)") (class "Default")
      (node (ref "*") (pin "35") (pinfunction "PB1_35") (pintype "passive+no_connect"))
    )
    (net (code "73") (name "unconnected-(*-PB13-Pad43)") (class "Default")
      (node (ref "*") (pin "43") (pinfunction "PB13_43") (pintype "passive+no_connect"))
    )
    (net (code "74") (name "unconnected-(*-PB14-Pad44)") (class "Default")
      (node (ref "*") (pin "44") (pinfunction "PB14_44") (pintype "passive+no_connect"))
    )
    (net (code "75") (name "unconnected-(*-PC3-Pad18)") (class "Default")
      (node (ref "*") (pin "18") (pinfunction "PC3_18") (pintype "passive+no_connect"))
    )
    (net (code "76") (name "unconnected-(*-PC4-Pad32)") (class "Default")
      (node (ref "*") (pin "32") (pinfunction "PC4_32") (pintype "passive+no_connect"))
    )
    (net (code "77") (name "unconnected-(*-PC5-Pad33)") (class "Default")
      (node (ref "*") (pin "33") (pinfunction "PC5_33") (pintype "passive+no_connect"))
    )
    (net (code "78") (name "unconnected-(*-PC13-ANTI_TAMP-Pad7)") (class "Default")
      (node (ref "*") (pin "7") (pinfunction "PC13-ANTI_TAMP_7") (pintype "passive+no_connect"))
    )
    (net (code "79") (name "unconnected-(*-PC14-OSC32_IN-Pad8)") (class "Default")
      (node (ref "*") (pin "8") (pinfunction "PC14-OSC32_IN_8") (pintype "passive+no_connect"))
    )
    (net (code "80") (name "unconnected-(*-PC15-OSC32_OUT-Pad9)") (class "Default")
      (node (ref "*") (pin "9") (pinfunction "PC15-OSC32_OUT_9") (pintype "passive+no_connect"))
    )
    (net (code "81") (name "unconnected-(*-PD1-Pad82)") (class "Default")
      (node (ref "*") (pin "82") (pinfunction "PD1_82") (pintype "passive"))
    )
    (net (code "82") (name "unconnected-(*-PD3-Pad84)") (class "Default")
      (node (ref "*") (pin "84") (pinfunction "PD3_84") (pintype "passive"))
    )
    (net (code "83") (name "unconnected-(*-PD4-Pad85)") (class "Default")
      (node (ref "*") (pin "85") (pinfunction "PD4_85") (pintype "passive"))
    )
    (net (code "84") (name "unconnected-(*-PD5-Pad86)") (class "Default")
      (node (ref "*") (pin "86") (pinfunction "PD5_86") (pintype "passive"))
    )
    (net (code "85") (name "unconnected-(*-PD6-Pad87)") (class "Default")
      (node (ref "*") (pin "87") (pinfunction "PD6_87") (pintype "passive"))
    )
    (net (code "86") (name "unconnected-(*-PD8-Pad55)") (class "Default")
      (node (ref "*") (pin "55") (pinfunction "PD8_55") (pintype "passive"))
    )
    (net (code "87") (name "unconnected-(*-PD9-Pad56)") (class "Default")
      (node (ref "*") (pin "56") (pinfunction "PD9_56") (pintype "passive"))
    )
    (net (code "88") (name "unconnected-(*-PD10-Pad57)") (class "Default")
      (node (ref "*") (pin "57") (pinfunction "PD10_57") (pintype "passive+no_connect"))
    )
    (net (code "89") (name "unconnected-(*-PD11-Pad58)") (class "Default")
      (node (ref "*") (pin "58") (pinfunction "PD11_58") (pintype "passive+no_connect"))
    )
    (net (code "90") (name "unconnected-(*-PD15-Pad62)") (class "Default")
      (node (ref "*") (pin "62") (pinfunction "PD15_62") (pintype "passive+no_connect"))
    )
    (net (code "91") (name "unconnected-(*-PE2-Pad1)") (class "Default")
      (node (ref "*") (pin "1") (pinfunction "PE2_1") (pintype "passive"))
    )
    (net (code "92") (name "unconnected-(*-PE3-Pad2)") (class "Default")
      (node (ref "*") (pin "2") (pinfunction "PE3_2") (pintype "passive+no_connect"))
    )
    (net (code "93") (name "unconnected-(*-PE7-Pad37)") (class "Default")
      (node (ref "*") (pin "37") (pinfunction "PE7_37") (pintype "passive+no_connect"))
    )
    (net (code "94") (name "unconnected-(*-PE8-Pad38)") (class "Default")
      (node (ref "*") (pin "38") (pinfunction "PE8_38") (pintype "passive+no_connect"))
    )
    (net (code "95") (name "unconnected-(*-PE9-Pad39)") (class "Default")
      (node (ref "*") (pin "39") (pinfunction "PE9_39") (pintype "passive+no_connect"))
    )
    (net (code "96") (name "unconnected-(*-PE10-Pad40)") (class "Default")
      (node (ref "*") (pin "40") (pinfunction "PE10_40") (pintype "passive+no_connect"))
    )
    (net (code "97") (name "unconnected-(*-PE11-Pad41)") (class "Default")
      (node (ref "*") (pin "41") (pinfunction "PE11_41") (pintype "passive+no_connect"))
    )
    (net (code "98") (name "unconnected-(*-PE12-Pad42)") (class "Default")
      (node (ref "*") (pin "42") (pinfunction "PE12_42") (pintype "passive+no_connect"))
    )
    (net (code "99") (name "unconnected-(*-PE15-Pad45)") (class "Default")
      (node (ref "*") (pin "45") (pinfunction "PE15_45") (pintype "passive+no_connect"))
    )
    (net (code "100") (name "unconnected-(FPC_7725-Pad24)") (class "Default")
      (node (ref "FPC_7725") (pin "24") (pinfunction "24_24") (pintype "passive+no_connect"))
    )
    (net (code "101") (name "unconnected-(FPC_MT9-Pad10)") (class "Default")
      (node (ref "FPC_MT9") (pin "10") (pinfunction "10_10") (pintype "passive+no_connect"))
    )
    (net (code "102") (name "unconnected-(J3-CC1-PadA5)") (class "Default")
      (node (ref "J3") (pin "A5") (pinfunction "CC1_A5") (pintype "passive"))
    )
    (net (code "103") (name "unconnected-(J3-CC2-PadB5)") (class "Default")
      (node (ref "J3") (pin "B5") (pinfunction "CC2_B5") (pintype "passive"))
    )
    (net (code "104") (name "unconnected-(J3-SBU1-PadA8)") (class "Default")
      (node (ref "J3") (pin "A8") (pinfunction "SBU1_A8") (pintype "passive"))
    )
    (net (code "105") (name "unconnected-(J3-SBU2-PadB8)") (class "Default")
      (node (ref "J3") (pin "B8") (pinfunction "SBU2_B8") (pintype "passive"))
    )
    (net (code "106") (name "unconnected-(J3-pad-Pad0)") (class "Default")
      (node (ref "J3") (pin "0") (pinfunction "pad_0") (pintype "passive+no_connect"))
    )
    (net (code "107") (name "unconnected-(J3-pad-Pad0)_1") (class "Default")
      (node (ref "J3") (pin "0") (pinfunction "pad_0") (pintype "passive+no_connect"))
    )
    (net (code "108") (name "unconnected-(J3-pad-Pad0)_2") (class "Default")
      (node (ref "J3") (pin "0") (pinfunction "pad_0") (pintype "passive+no_connect"))
    )
    (net (code "109") (name "unconnected-(J3-pad-Pad0)_3") (class "Default")
      (node (ref "J3") (pin "0") (pinfunction "pad_0") (pintype "passive+no_connect"))
    )
    (net (code "110") (name "unconnected-(U2-BYP-Pad4)") (class "Default")
      (node (ref "U2") (pin "4") (pinfunction "BYP_4") (pintype "passive"))
    )
  )
)
